# SMD_cree_driver_led-mosfet002.net
KiCad netlist of a schematic drawn in EAGLE
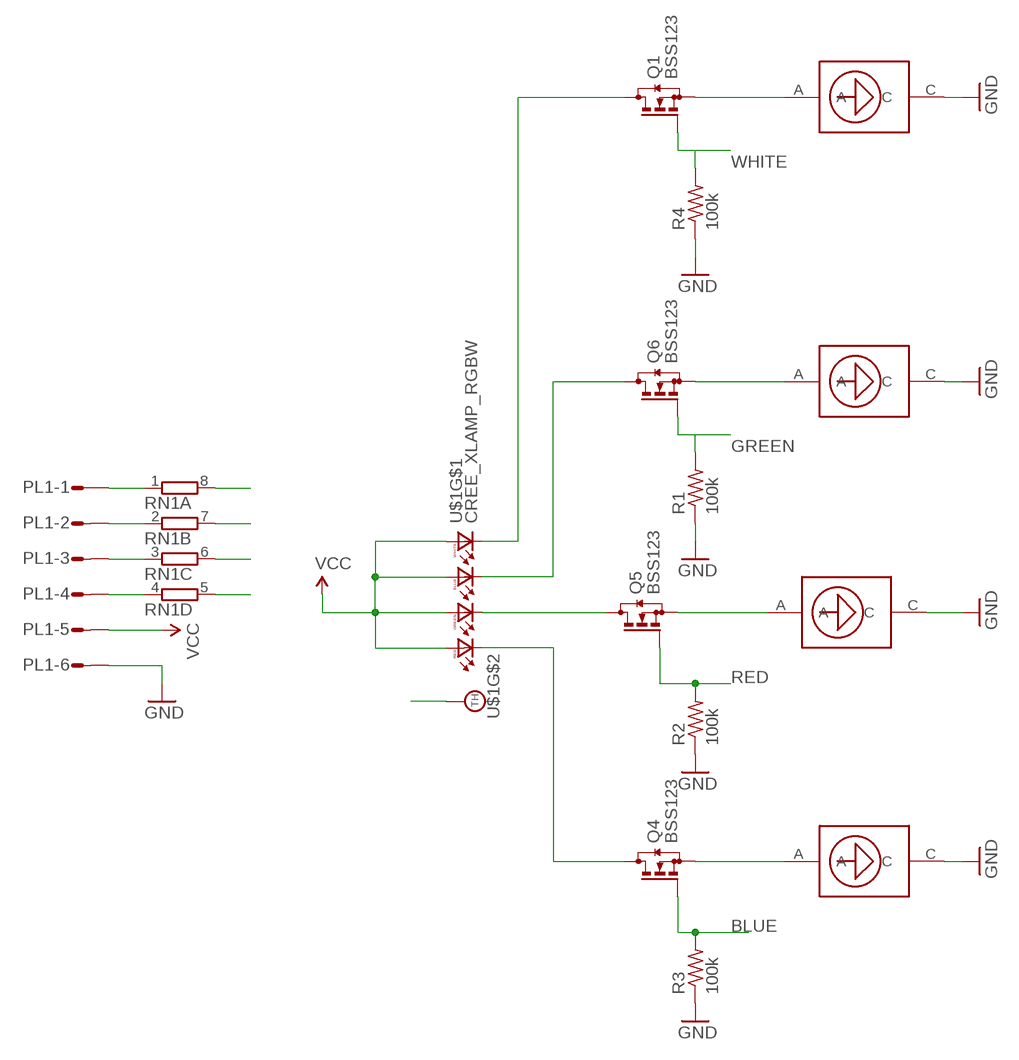
[diagram p0: schematic, sheet 1]

(export (version "E")
  (design (tool "Eeschema 10.0.6"))
  (components
    (comp (ref "PL1")
      (value "DF3-06R")
      (footprint "eagle-import:DF3R-06")
      (libsource (lib "eagle-import") (part "DF3-06R"))
    )
    (comp (ref "Q1")
      (value "BSS123")
      (footprint "eagle-import:SOT23")
      (libsource (lib "eagle-import") (part "BSS123"))
    )
    (comp (ref "Q4")
      (value "BSS123")
      (footprint "eagle-import:SOT23")
      (libsource (lib "eagle-import") (part "BSS123"))
    )
    (comp (ref "Q5")
      (value "BSS123")
      (footprint "eagle-import:SOT23")
      (libsource (lib "eagle-import") (part "BSS123"))
    )
    (comp (ref "Q6")
      (value "BSS123")
      (footprint "eagle-import:SOT23")
      (libsource (lib "eagle-import") (part "BSS123"))
    )
    (comp (ref "R1")
      (value "100k")
      (footprint "eagle-import:R0402")
      (libsource (lib "eagle-import") (part "R-US_R0402"))
    )
    (comp (ref "R2")
      (value "100k")
      (footprint "eagle-import:R0402")
      (libsource (lib "eagle-import") (part "R-US_R0402"))
    )
    (comp (ref "R3")
      (value "100k")
      (footprint "eagle-import:R0402")
      (libsource (lib "eagle-import") (part "R-US_R0402"))
    )
    (comp (ref "R4")
      (value "100k")
      (footprint "eagle-import:R0402")
      (libsource (lib "eagle-import") (part "R-US_R0402"))
    )
    (comp (ref "RN1")
      (value "4R-N0603-ARC")
      (footprint "eagle-import:0603-ARC")
      (libsource (lib "eagle-import") (part "4R-N0603-ARC"))
    )
    (comp (ref "U$1")
      (value "CREE_XLAMP_RGBW")
      (footprint "eagle-import:CREE_XLAMP_XML")
      (libsource (lib "eagle-import") (part "CREE_XLAMP_RGBW"))
    )
    (comp (ref "U$2")
      (value "NSI50350AST3G")
      (footprint "eagle-import:SMC-2")
      (libsource (lib "eagle-import") (part "NSI50350AST3G"))
    )
    (comp (ref "U$3")
      (value "NSI50350AST3G")
      (footprint "eagle-import:SMC-2")
      (libsource (lib "eagle-import") (part "NSI50350AST3G"))
    )
    (comp (ref "U$4")
      (value "NSI50350AST3G")
      (footprint "eagle-import:SMC-2")
      (libsource (lib "eagle-import") (part "NSI50350AST3G"))
    )
    (comp (ref "U$5")
      (value "NSI50350AST3G")
      (footprint "eagle-import:SMC-2")
      (libsource (lib "eagle-import") (part "NSI50350AST3G"))
    )
  )
  (nets
    (net (code "1") (name "/BLUE") (class "Default")
      (node (ref "Q4") (pin "1") (pinfunction "G_1") (pintype "passive"))
      (node (ref "R3") (pin "2") (pinfunction "2_2") (pintype "passive"))
      (node (ref "RN1") (pin "7") (pinfunction "2_7") (pintype "passive"))
    )
    (net (code "2") (name "/GREEN") (class "Default")
      (node (ref "Q6") (pin "1") (pinfunction "G_1") (pintype "passive"))
      (node (ref "R1") (pin "2") (pinfunction "2_2") (pintype "passive"))
      (node (ref "RN1") (pin "6") (pinfunction "2_6") (pintype "passive"))
    )
    (net (code "3") (name "/RED") (class "Default")
      (node (ref "Q5") (pin "1") (pinfunction "G_1") (pintype "passive"))
      (node (ref "R2") (pin "2") (pinfunction "2_2") (pintype "passive"))
      (node (ref "RN1") (pin "5") (pinfunction "2_5") (pintype "passive"))
    )
    (net (code "4") (name "/WHITE") (class "Default")
      (node (ref "Q1") (pin "1") (pinfunction "G_1") (pintype "passive"))
      (node (ref "R4") (pin "2") (pinfunction "2_2") (pintype "passive"))
      (node (ref "RN1") (pin "8") (pinfunction "2_8") (pintype "passive"))
    )
    (net (code "5") (name "GND") (class "Default")
      (node (ref "PL1") (pin "6") (pinfunction "S_6") (pintype "passive"))
      (node (ref "R1") (pin "1") (pinfunction "1_1") (pintype "passive"))
      (node (ref "R2") (pin "1") (pinfunction "1_1") (pintype "passive"))
      (node (ref "R3") (pin "1") (pinfunction "1_1") (pintype "passive"))
      (node (ref "R4") (pin "1") (pinfunction "1_1") (pintype "passive"))
      (node (ref "U$2") (pin "C") (pinfunction "C_C") (pintype "bidirectional"))
      (node (ref "U$3") (pin "C") (pinfunction "C_C") (pintype "bidirectional"))
      (node (ref "U$4") (pin "C") (pinfunction "C_C") (pintype "bidirectional"))
      (node (ref "U$5") (pin "C") (pinfunction "C_C") (pintype "bidirectional"))
    )
    (net (code "6") (name "Net-(PL1A-S)") (class "Default")
      (node (ref "PL1") (pin "1") (pinfunction "S_1") (pintype "passive"))
      (node (ref "RN1") (pin "1") (pinfunction "1_1") (pintype "passive"))
    )
    (net (code "7") (name "Net-(PL1B-S)") (class "Default")
      (node (ref "PL1") (pin "2") (pinfunction "S_2") (pintype "passive"))
      (node (ref "RN1") (pin "2") (pinfunction "1_2") (pintype "passive"))
    )
    (net (code "8") (name "Net-(PL1C-S)") (class "Default")
      (node (ref "PL1") (pin "3") (pinfunction "S_3") (pintype "passive"))
      (node (ref "RN1") (pin "3") (pinfunction "1_3") (pintype "passive"))
    )
    (net (code "9") (name "Net-(PL1D-S)") (class "Default")
      (node (ref "PL1") (pin "4") (pinfunction "S_4") (pintype "passive"))
      (node (ref "RN1") (pin "4") (pinfunction "1_4") (pintype "passive"))
    )
    (net (code "10") (name "Net-(Q1-D)") (class "Default")
      (node (ref "Q1") (pin "3") (pinfunction "D_3") (pintype "passive"))
      (node (ref "U$1") (pin "5") (pinfunction "WC_5") (pintype "passive"))
    )
    (net (code "11") (name "Net-(Q1-S)") (class "Default")
      (node (ref "Q1") (pin "2") (pinfunction "S_2") (pintype "passive"))
      (node (ref "U$5") (pin "A") (pinfunction "A_A") (pintype "bidirectional"))
    )
    (net (code "12") (name "Net-(Q4-D)") (class "Default")
      (node (ref "Q4") (pin "3") (pinfunction "D_3") (pintype "passive"))
      (node (ref "U$1") (pin "8") (pinfunction "RC_8") (pintype "passive"))
    )
    (net (code "13") (name "Net-(Q4-S)") (class "Default")
      (node (ref "Q4") (pin "2") (pinfunction "S_2") (pintype "passive"))
      (node (ref "U$4") (pin "A") (pinfunction "A_A") (pintype "bidirectional"))
    )
    (net (code "14") (name "Net-(Q5-D)") (class "Default")
      (node (ref "Q5") (pin "3") (pinfunction "D_3") (pintype "passive"))
      (node (ref "U$1") (pin "7") (pinfunction "GC_7") (pintype "passive"))
    )
    (net (code "15") (name "Net-(Q5-S)") (class "Default")
      (node (ref "Q5") (pin "2") (pinfunction "S_2") (pintype "passive"))
      (node (ref "U$3") (pin "A") (pinfunction "A_A") (pintype "bidirectional"))
    )
    (net (code "16") (name "Net-(Q6-D)") (class "Default")
      (node (ref "Q6") (pin "3") (pinfunction "D_3") (pintype "passive"))
      (node (ref "U$1") (pin "6") (pinfunction "BC_6") (pintype "passive"))
    )
    (net (code "17") (name "Net-(Q6-S)") (class "Default")
      (node (ref "Q6") (pin "2") (pinfunction "S_2") (pintype "passive"))
      (node (ref "U$2") (pin "A") (pinfunction "A_A") (pintype "bidirectional"))
    )
    (net (code "18") (name "VCC") (class "Default")
      (node (ref "PL1") (pin "5") (pinfunction "S_5") (pintype "passive"))
      (node (ref "U$1") (pin "1") (pinfunction "RA_1") (pintype "passive"))
      (node (ref "U$1") (pin "2") (pinfunction "GA_2") (pintype "passive"))
      (node (ref "U$1") (pin "3") (pinfunction "BA_3") (pintype "passive"))
      (node (ref "U$1") (pin "4") (pinfunction "WA_4") (pintype "passive"))
    )
    (net (code "19") (name "unconnected-(U$1B-TH-PadP$1)") (class "Default")
      (node (ref "U$1") (pin "P$1") (pinfunction "TH_P$1") (pintype "passive"))
    )
  )
)
